# segment.net
KiCad netlist of a schematic drawn in EAGLE
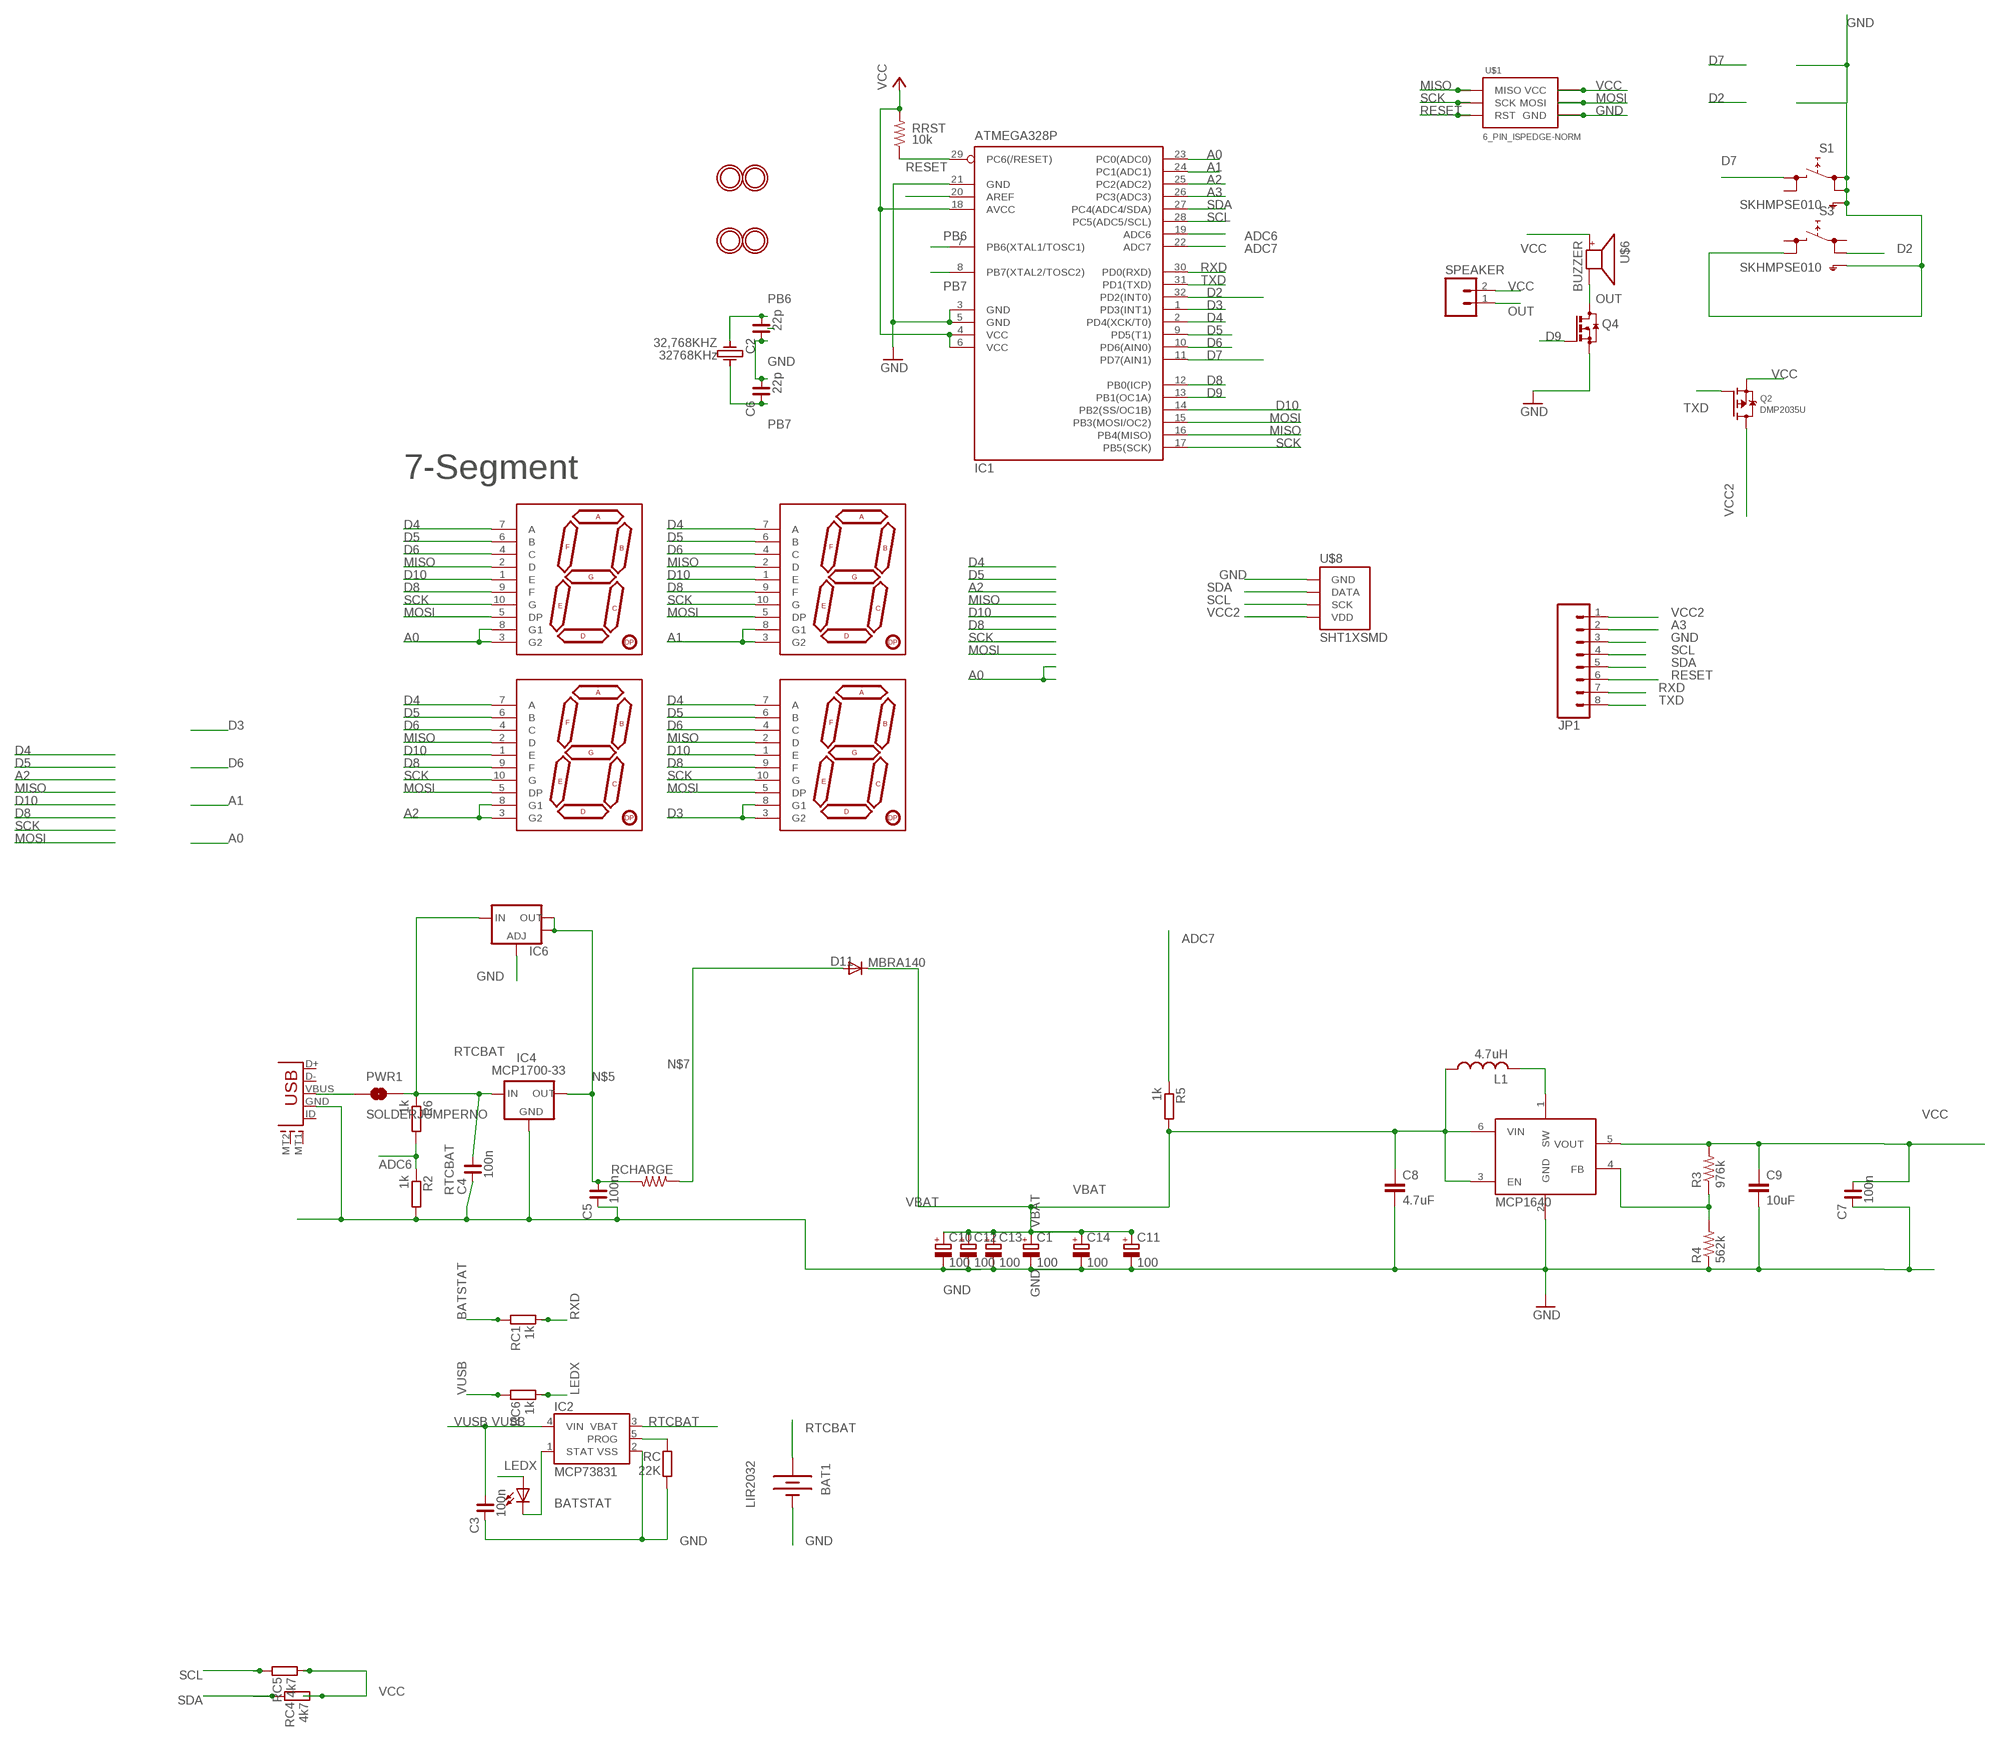
[diagram p0: schematic, sheet 1]

(export (version "E")
  (design (tool "Eeschema 10.0.6"))
  (components
    (comp (ref "32,768KHZ")
      (value "32768KHz")
      (footprint "eagle-import:KX-327LT")
      (libsource (lib "eagle-import") (part "CRYSTALL"))
    )
    (comp (ref "BAT1")
      (value "LIR2032")
      (footprint "eagle-import:BATTCOM_20MM_PTH_SMT")
      (libsource (lib "eagle-import") (part "BATTERYBATTCOM_20MM_PTH_SMT"))
    )
    (comp (ref "C1")
      (value "100")
      (footprint "eagle-import:TT5D11L")
      (libsource (lib "eagle-import") (part "CPOL-EUTT5D11L"))
    )
    (comp (ref "C2")
      (value "22p")
      (footprint "eagle-import:C0603")
      (libsource (lib "eagle-import") (part "C_0603"))
    )
    (comp (ref "C3")
      (value "100n")
      (footprint "eagle-import:C0603")
      (libsource (lib "eagle-import") (part "C_0603"))
    )
    (comp (ref "C4")
      (value "100n")
      (footprint "eagle-import:C0603")
      (libsource (lib "eagle-import") (part "C_0603"))
    )
    (comp (ref "C5")
      (value "100n")
      (footprint "eagle-import:C0603")
      (libsource (lib "eagle-import") (part "C_0603"))
    )
    (comp (ref "C6")
      (value "22p")
      (footprint "eagle-import:C0603")
      (libsource (lib "eagle-import") (part "C_0603"))
    )
    (comp (ref "C7")
      (value "100n")
      (footprint "eagle-import:C0603")
      (libsource (lib "eagle-import") (part "C_0603"))
    )
    (comp (ref "C8")
      (value "4.7uF")
      (footprint "eagle-import:0805")
      (libsource (lib "eagle-import") (part "CAP0805"))
    )
    (comp (ref "C9")
      (value "10uF")
      (footprint "eagle-import:0805")
      (libsource (lib "eagle-import") (part "CAP0805"))
    )
    (comp (ref "C10")
      (value "100")
      (footprint "eagle-import:TT5D11L")
      (libsource (lib "eagle-import") (part "CPOL-EUTT5D11L"))
    )
    (comp (ref "C11")
      (value "100")
      (footprint "eagle-import:TT5D11L")
      (libsource (lib "eagle-import") (part "CPOL-EUTT5D11L"))
    )
    (comp (ref "C12")
      (value "100")
      (footprint "eagle-import:TT5D11L")
      (libsource (lib "eagle-import") (part "CPOL-EUTT5D11L"))
    )
    (comp (ref "C13")
      (value "100")
      (footprint "eagle-import:TT5D11L")
      (libsource (lib "eagle-import") (part "CPOL-EUTT5D11L"))
    )
    (comp (ref "C14")
      (value "100")
      (footprint "eagle-import:TT5D11L")
      (libsource (lib "eagle-import") (part "CPOL-EUTT5D11L"))
    )
    (comp (ref "CHG")
      (value "0805")
      (footprint "eagle-import:CHIPLED_0603")
      (libsource (lib "eagle-import") (part "LEDCHIPLED_0603"))
    )
    (comp (ref "D11")
      (value "MBRA140")
      (footprint "eagle-import:SOD-323")
      (libsource (lib "eagle-import") (part "DIODESOD"))
    )
    (comp (ref "DIG1")
      (value "7-SEGMENT-DISPLAY-1\"-RED")
      (footprint "eagle-import:7-SEGMENT-SMD")
      (libsource (lib "eagle-import") (part "7-SEGMENT-DISPLAY-1{dblquote}-RED"))
    )
    (comp (ref "DIG2")
      (value "7-SEGMENT-DISPLAY-1\"-RED")
      (footprint "eagle-import:7-SEGMENT-SMD")
      (libsource (lib "eagle-import") (part "7-SEGMENT-DISPLAY-1{dblquote}-RED"))
    )
    (comp (ref "DIG3")
      (value "7-SEGMENT-DISPLAY-1\"-RED")
      (footprint "eagle-import:7-SEGMENT-SMD")
      (libsource (lib "eagle-import") (part "7-SEGMENT-DISPLAY-1{dblquote}-RED"))
    )
    (comp (ref "DIG4")
      (value "7-SEGMENT-DISPLAY-1\"-RED")
      (footprint "eagle-import:7-SEGMENT-SMD")
      (libsource (lib "eagle-import") (part "7-SEGMENT-DISPLAY-1{dblquote}-RED"))
    )
    (comp (ref "IC1")
      (value "ATMEGA328P")
      (footprint "eagle-import:TQFP32-08")
      (fields (field (name "MPN") "ATMEGA8-16AU"))
      (libsource (lib "eagle-import") (part "MEGA8-AI"))
    )
    (comp (ref "IC2")
      (value "MCP73831")
      (footprint "eagle-import:SOT23-5")
      (libsource (lib "eagle-import") (part "MCP73831"))
    )
    (comp (ref "IC4")
      (value "MCP1700-33")
      (footprint "eagle-import:SOT23")
      (libsource (lib "eagle-import") (part "MCP1700SOT233"))
    )
    (comp (ref "IC6")
      (value "V_REG_LM1117SOT223")
      (footprint "eagle-import:SOT223")
      (libsource (lib "eagle-import") (part "V_REG_LM1117SOT223"))
    )
    (comp (ref "JP1")
      (value "M08NO_SILK")
      (footprint "eagle-import:1X08_PIN1_NO_SILK")
      (libsource (lib "eagle-import") (part "M08NO_SILK"))
    )
    (comp (ref "L1")
      (value "4.7uH")
      (footprint "eagle-import:LQH44")
      (libsource (lib "eagle-import") (part "LLQH44P_P0"))
    )
    (comp (ref "PWR1")
      (value "SOLDERJUMPERNO")
      (footprint "eagle-import:SJ_2S-NO")
      (libsource (lib "eagle-import") (part "SOLDERJUMPERNO"))
    )
    (comp (ref "Q2")
      (value "DMP2035U")
      (footprint "eagle-import:SOT23-WIDE")
      (libsource (lib "eagle-import") (part "MOSFET-PWIDE"))
    )
    (comp (ref "Q4")
      (value "BSS123")
      (footprint "eagle-import:SOT23")
      (libsource (lib "eagle-import") (part "BSS123"))
    )
    (comp (ref "R2")
      (value "1k")
      (footprint "eagle-import:R0603")
      (libsource (lib "eagle-import") (part "R-EU_R0603"))
    )
    (comp (ref "R3")
      (value "976k")
      (footprint "eagle-import:0603-RES")
      (libsource (lib "eagle-import") (part "RESISTOR0603-RES"))
    )
    (comp (ref "R4")
      (value "562k")
      (footprint "eagle-import:0603-RES")
      (libsource (lib "eagle-import") (part "RESISTOR0603-RES"))
    )
    (comp (ref "R5")
      (value "1k")
      (footprint "eagle-import:R0603")
      (libsource (lib "eagle-import") (part "R-EU_R0603"))
    )
    (comp (ref "R6")
      (value "1k")
      (footprint "eagle-import:R0603")
      (libsource (lib "eagle-import") (part "R-EU_R0603"))
    )
    (comp (ref "RC")
      (value "22K")
      (footprint "eagle-import:R0603")
      (libsource (lib "eagle-import") (part "R-EU_R0603"))
    )
    (comp (ref "RC1")
      (value "1k")
      (footprint "eagle-import:R0603")
      (libsource (lib "eagle-import") (part "R-EU_R0603"))
    )
    (comp (ref "RC4")
      (value "4k7")
      (footprint "eagle-import:R0603")
      (libsource (lib "eagle-import") (part "R-EU_R0603"))
    )
    (comp (ref "RC5")
      (value "4k7")
      (footprint "eagle-import:R0603")
      (libsource (lib "eagle-import") (part "R-EU_R0603"))
    )
    (comp (ref "RC6")
      (value "1k")
      (footprint "eagle-import:R0603")
      (libsource (lib "eagle-import") (part "R-EU_R0603"))
    )
    (comp (ref "RCHARGE")
      (value "RESISTOR1206")
      (footprint "eagle-import:1206")
      (libsource (lib "eagle-import") (part "RESISTOR1206"))
    )
    (comp (ref "RRST")
      (value "10k")
      (footprint "eagle-import:R0603@1")
      (libsource (lib "eagle-import") (part "R-US_R0603"))
    )
    (comp (ref "S1")
      (value "SKHMPSE010")
      (footprint "eagle-import:SKHMPXE010")
      (libsource (lib "eagle-import") (part "SKHMPE010S"))
    )
    (comp (ref "S3")
      (value "SKHMPSE010")
      (footprint "eagle-import:SKHMPXE010")
      (libsource (lib "eagle-import") (part "SKHMPE010S"))
    )
    (comp (ref "SPEAKER")
      (value "M02PTH")
      (footprint "eagle-import:1X02")
      (libsource (lib "eagle-import") (part "M02PTH"))
    )
    (comp (ref "U$1")
      (value "6_PIN_ISPEDGE-NORM")
      (footprint "eagle-import:6_PIN_EDGE")
      (libsource (lib "eagle-import") (part "6_PIN_ISPEDGE-NORM"))
    )
    (comp (ref "U$2")
      (value "MOUNTINGHOLE2.0")
      (footprint "eagle-import:MOUNTINGHOLE_2.0_PLATED")
      (libsource (lib "eagle-import") (part "MOUNTINGHOLE2.0"))
    )
    (comp (ref "U$3")
      (value "MOUNTINGHOLE2.0")
      (footprint "eagle-import:MOUNTINGHOLE_2.0_PLATED")
      (libsource (lib "eagle-import") (part "MOUNTINGHOLE2.0"))
    )
    (comp (ref "U$4")
      (value "MOUNTINGHOLE2.0")
      (footprint "eagle-import:MOUNTINGHOLE_2.0_PLATED")
      (libsource (lib "eagle-import") (part "MOUNTINGHOLE2.0"))
    )
    (comp (ref "U$5")
      (value "MOUNTINGHOLE2.0")
      (footprint "eagle-import:MOUNTINGHOLE_2.0_PLATED")
      (libsource (lib "eagle-import") (part "MOUNTINGHOLE2.0"))
    )
    (comp (ref "U$6")
      (value "BUZZER")
      (footprint "eagle-import:SMT-8585-BUZZER")
      (libsource (lib "eagle-import") (part "BUZZER"))
    )
    (comp (ref "U$8")
      (value "SHT1XSMD")
      (footprint "eagle-import:SHT1X")
      (libsource (lib "eagle-import") (part "SHT1XSMD"))
    )
    (comp (ref "U2")
      (value "MCP1640")
      (footprint "eagle-import:SOT23-6")
      (libsource (lib "eagle-import") (part "MCP1640"))
    )
    (comp (ref "USB2")
      (value "USB-MICROBLARGEPAD")
      (footprint "eagle-import:USB-MICROB_LARGEPAD")
      (libsource (lib "eagle-import") (part "USB-MICROBLARGEPAD"))
    )
  )
  (nets
    (net (code "1") (name "/A0") (class "Default")
      (node (ref "DIG1") (pin "3") (pinfunction "G2_3") (pintype "bidirectional"))
      (node (ref "DIG1") (pin "8") (pinfunction "G1_8") (pintype "bidirectional"))
      (node (ref "IC1") (pin "23") (pinfunction "PC0(ADC0)_23") (pintype "bidirectional"))
    )
    (net (code "2") (name "/A1") (class "Default")
      (node (ref "DIG2") (pin "3") (pinfunction "G2_3") (pintype "bidirectional"))
      (node (ref "DIG2") (pin "8") (pinfunction "G1_8") (pintype "bidirectional"))
      (node (ref "IC1") (pin "24") (pinfunction "PC1(ADC1)_24") (pintype "bidirectional"))
    )
    (net (code "3") (name "/A2") (class "Default")
      (node (ref "DIG3") (pin "3") (pinfunction "G2_3") (pintype "bidirectional"))
      (node (ref "DIG3") (pin "8") (pinfunction "G1_8") (pintype "bidirectional"))
      (node (ref "IC1") (pin "25") (pinfunction "PC2(ADC2)_25") (pintype "bidirectional"))
    )
    (net (code "4") (name "/A3") (class "Default")
      (node (ref "IC1") (pin "26") (pinfunction "PC3(ADC3)_26") (pintype "bidirectional"))
      (node (ref "JP1") (pin "2") (pinfunction "2_2") (pintype "passive"))
    )
    (net (code "5") (name "/ADC6") (class "Default")
      (node (ref "IC1") (pin "19") (pinfunction "ADC6_19") (pintype "bidirectional"))
      (node (ref "R2") (pin "1") (pinfunction "1_1") (pintype "passive"))
      (node (ref "R6") (pin "2") (pinfunction "2_2") (pintype "passive"))
    )
    (net (code "6") (name "/ADC7") (class "Default")
      (node (ref "IC1") (pin "22") (pinfunction "ADC7_22") (pintype "bidirectional"))
      (node (ref "R5") (pin "1") (pinfunction "1_1") (pintype "passive"))
    )
    (net (code "7") (name "/BATSTAT") (class "Default")
      (node (ref "CHG") (pin "C") (pinfunction "C_C") (pintype "passive"))
      (node (ref "IC2") (pin "1") (pinfunction "STAT_1") (pintype "output"))
      (node (ref "RC1") (pin "2") (pinfunction "2_2") (pintype "passive"))
    )
    (net (code "8") (name "/D2") (class "Default")
      (node (ref "IC1") (pin "32") (pinfunction "PD2(INT0)_32") (pintype "bidirectional"))
      (node (ref "S3") (pin "2") (pinfunction "1.2_2") (pintype "passive"))
    )
    (net (code "9") (name "/D3") (class "Default")
      (node (ref "DIG4") (pin "3") (pinfunction "G2_3") (pintype "bidirectional"))
      (node (ref "DIG4") (pin "8") (pinfunction "G1_8") (pintype "bidirectional"))
      (node (ref "IC1") (pin "1") (pinfunction "PD3(INT1)_1") (pintype "bidirectional"))
    )
    (net (code "10") (name "/D4") (class "Default")
      (node (ref "DIG1") (pin "7") (pinfunction "A_7") (pintype "bidirectional"))
      (node (ref "DIG2") (pin "7") (pinfunction "A_7") (pintype "bidirectional"))
      (node (ref "DIG3") (pin "7") (pinfunction "A_7") (pintype "bidirectional"))
      (node (ref "DIG4") (pin "7") (pinfunction "A_7") (pintype "bidirectional"))
      (node (ref "IC1") (pin "2") (pinfunction "PD4(XCK/T0)_2") (pintype "bidirectional"))
    )
    (net (code "11") (name "/D5") (class "Default")
      (node (ref "DIG1") (pin "6") (pinfunction "B_6") (pintype "bidirectional"))
      (node (ref "DIG2") (pin "6") (pinfunction "B_6") (pintype "bidirectional"))
      (node (ref "DIG3") (pin "6") (pinfunction "B_6") (pintype "bidirectional"))
      (node (ref "DIG4") (pin "6") (pinfunction "B_6") (pintype "bidirectional"))
      (node (ref "IC1") (pin "9") (pinfunction "PD5(T1)_9") (pintype "bidirectional"))
    )
    (net (code "12") (name "/D6") (class "Default")
      (node (ref "DIG1") (pin "4") (pinfunction "C_4") (pintype "bidirectional"))
      (node (ref "DIG2") (pin "4") (pinfunction "C_4") (pintype "bidirectional"))
      (node (ref "DIG3") (pin "4") (pinfunction "C_4") (pintype "bidirectional"))
      (node (ref "DIG4") (pin "4") (pinfunction "C_4") (pintype "bidirectional"))
      (node (ref "IC1") (pin "10") (pinfunction "PD6(AIN0)_10") (pintype "bidirectional"))
    )
    (net (code "13") (name "/D7") (class "Default")
      (node (ref "IC1") (pin "11") (pinfunction "PD7(AIN1)_11") (pintype "bidirectional"))
      (node (ref "S1") (pin "3") (pinfunction "2.1_3") (pintype "passive"))
    )
    (net (code "14") (name "/D8") (class "Default")
      (node (ref "DIG1") (pin "9") (pinfunction "F_9") (pintype "bidirectional"))
      (node (ref "DIG2") (pin "9") (pinfunction "F_9") (pintype "bidirectional"))
      (node (ref "DIG3") (pin "9") (pinfunction "F_9") (pintype "bidirectional"))
      (node (ref "DIG4") (pin "9") (pinfunction "F_9") (pintype "bidirectional"))
      (node (ref "IC1") (pin "12") (pinfunction "PB0(ICP)_12") (pintype "bidirectional"))
    )
    (net (code "15") (name "/D9") (class "Default")
      (node (ref "IC1") (pin "13") (pinfunction "PB1(OC1A)_13") (pintype "bidirectional"))
      (node (ref "Q4") (pin "1") (pinfunction "G_1") (pintype "passive"))
    )
    (net (code "16") (name "/D10") (class "Default")
      (node (ref "DIG1") (pin "1") (pinfunction "E_1") (pintype "bidirectional"))
      (node (ref "DIG2") (pin "1") (pinfunction "E_1") (pintype "bidirectional"))
      (node (ref "DIG3") (pin "1") (pinfunction "E_1") (pintype "bidirectional"))
      (node (ref "DIG4") (pin "1") (pinfunction "E_1") (pintype "bidirectional"))
      (node (ref "IC1") (pin "14") (pinfunction "PB2(SS/OC1B)_14") (pintype "bidirectional"))
    )
    (net (code "17") (name "/LEDX") (class "Default")
      (node (ref "CHG") (pin "A") (pinfunction "A_A") (pintype "passive"))
      (node (ref "RC6") (pin "1") (pinfunction "1_1") (pintype "passive"))
    )
    (net (code "18") (name "/MISO") (class "Default")
      (node (ref "DIG1") (pin "2") (pinfunction "D_2") (pintype "bidirectional"))
      (node (ref "DIG2") (pin "2") (pinfunction "D_2") (pintype "bidirectional"))
      (node (ref "DIG3") (pin "2") (pinfunction "D_2") (pintype "bidirectional"))
      (node (ref "DIG4") (pin "2") (pinfunction "D_2") (pintype "bidirectional"))
      (node (ref "IC1") (pin "16") (pinfunction "PB4(MISO)_16") (pintype "bidirectional"))
      (node (ref "U$1") (pin "1") (pinfunction "MISO_1") (pintype "bidirectional"))
    )
    (net (code "19") (name "/MOSI") (class "Default")
      (node (ref "DIG1") (pin "5") (pinfunction "DP_5") (pintype "bidirectional"))
      (node (ref "DIG2") (pin "5") (pinfunction "DP_5") (pintype "bidirectional"))
      (node (ref "DIG3") (pin "5") (pinfunction "DP_5") (pintype "bidirectional"))
      (node (ref "DIG4") (pin "5") (pinfunction "DP_5") (pintype "bidirectional"))
      (node (ref "IC1") (pin "15") (pinfunction "PB3(MOSI/OC2)_15") (pintype "bidirectional"))
      (node (ref "U$1") (pin "4") (pinfunction "MOSI_4") (pintype "bidirectional"))
    )
    (net (code "20") (name "/N$5") (class "Default")
      (node (ref "C5") (pin "1") (pinfunction "1_1") (pintype "passive"))
      (node (ref "IC4") (pin "2") (pinfunction "OUT_2") (pintype "passive"))
      (node (ref "IC6") (pin "2") (pinfunction "OUT_2") (pintype "output"))
      (node (ref "IC6") (pin "4") (pinfunction "OUT_4") (pintype "output"))
      (node (ref "RCHARGE") (pin "2") (pinfunction "2_2") (pintype "passive"))
    )
    (net (code "21") (name "/N$7") (class "Default")
      (node (ref "D11") (pin "2") (pinfunction "A_2") (pintype "passive"))
      (node (ref "RCHARGE") (pin "1") (pinfunction "1_1") (pintype "passive"))
    )
    (net (code "22") (name "/OUT") (class "Default")
      (node (ref "Q4") (pin "3") (pinfunction "D_3") (pintype "passive"))
      (node (ref "SPEAKER") (pin "1") (pinfunction "1_1") (pintype "passive"))
      (node (ref "U$6") (pin "-") (pinfunction "-_-") (pintype "passive"))
    )
    (net (code "23") (name "/PB6") (class "Default")
      (node (ref "32,768KHZ") (pin "4") (pinfunction "P$2_4") (pintype "bidirectional"))
      (node (ref "C2") (pin "1") (pinfunction "1_1") (pintype "passive"))
      (node (ref "IC1") (pin "7") (pinfunction "PB6(XTAL1/TOSC1)_7") (pintype "bidirectional"))
    )
    (net (code "24") (name "/PB7") (class "Default")
      (node (ref "32,768KHZ") (pin "1") (pinfunction "P$1_1") (pintype "bidirectional"))
      (node (ref "C6") (pin "2") (pinfunction "2_2") (pintype "passive"))
      (node (ref "IC1") (pin "8") (pinfunction "PB7(XTAL2/TOSC2)_8") (pintype "bidirectional"))
    )
    (net (code "25") (name "/RESET") (class "Default")
      (node (ref "IC1") (pin "29") (pinfunction "PC6(/RESET)_29") (pintype "bidirectional"))
      (node (ref "JP1") (pin "6") (pinfunction "6_6") (pintype "passive"))
      (node (ref "RRST") (pin "1") (pinfunction "1_1") (pintype "passive"))
      (node (ref "U$1") (pin "5") (pinfunction "RST_5") (pintype "bidirectional"))
    )
    (net (code "26") (name "/RTCBAT") (class "Default")
      (node (ref "BAT1") (pin "P$2") (pinfunction "+_P$2") (pintype "power_in"))
      (node (ref "C4") (pin "1") (pinfunction "1_1") (pintype "passive"))
      (node (ref "IC2") (pin "3") (pinfunction "VBAT_3") (pintype "power_in"))
      (node (ref "IC4") (pin "3") (pinfunction "IN_3") (pintype "input"))
      (node (ref "IC6") (pin "3") (pinfunction "IN_3") (pintype "input"))
      (node (ref "PWR1") (pin "2") (pinfunction "2_2") (pintype "passive"))
      (node (ref "R6") (pin "1") (pinfunction "1_1") (pintype "passive"))
    )
    (net (code "27") (name "/RXD") (class "Default")
      (node (ref "IC1") (pin "30") (pinfunction "PD0(RXD)_30") (pintype "bidirectional"))
      (node (ref "JP1") (pin "7") (pinfunction "7_7") (pintype "passive"))
      (node (ref "RC1") (pin "1") (pinfunction "1_1") (pintype "passive"))
    )
    (net (code "28") (name "/SCK") (class "Default")
      (node (ref "DIG1") (pin "10") (pinfunction "G_10") (pintype "bidirectional"))
      (node (ref "DIG2") (pin "10") (pinfunction "G_10") (pintype "bidirectional"))
      (node (ref "DIG3") (pin "10") (pinfunction "G_10") (pintype "bidirectional"))
      (node (ref "DIG4") (pin "10") (pinfunction "G_10") (pintype "bidirectional"))
      (node (ref "IC1") (pin "17") (pinfunction "PB5(SCK)_17") (pintype "bidirectional"))
      (node (ref "U$1") (pin "3") (pinfunction "SCK_3") (pintype "bidirectional"))
    )
    (net (code "29") (name "/SCL") (class "Default")
      (node (ref "IC1") (pin "28") (pinfunction "PC5(ADC5/SCL)_28") (pintype "bidirectional"))
      (node (ref "JP1") (pin "4") (pinfunction "4_4") (pintype "passive"))
      (node (ref "RC5") (pin "2") (pinfunction "2_2") (pintype "passive"))
      (node (ref "U$8") (pin "3") (pinfunction "SCK_3") (pintype "input"))
    )
    (net (code "30") (name "/SDA") (class "Default")
      (node (ref "IC1") (pin "27") (pinfunction "PC4(ADC4/SDA)_27") (pintype "bidirectional"))
      (node (ref "JP1") (pin "5") (pinfunction "5_5") (pintype "passive"))
      (node (ref "RC4") (pin "2") (pinfunction "2_2") (pintype "passive"))
      (node (ref "U$8") (pin "2") (pinfunction "DATA_2") (pintype "bidirectional"))
    )
    (net (code "31") (name "/TXD") (class "Default")
      (node (ref "IC1") (pin "31") (pinfunction "PD1(TXD)_31") (pintype "bidirectional"))
      (node (ref "JP1") (pin "8") (pinfunction "8_8") (pintype "passive"))
      (node (ref "Q2") (pin "1") (pinfunction "G_1") (pintype "passive"))
    )
    (net (code "32") (name "/VBAT") (class "Default")
      (node (ref "C1") (pin "+") (pinfunction "+_+") (pintype "passive"))
      (node (ref "C10") (pin "+") (pinfunction "+_+") (pintype "passive"))
      (node (ref "C11") (pin "+") (pinfunction "+_+") (pintype "passive"))
      (node (ref "C12") (pin "+") (pinfunction "+_+") (pintype "passive"))
      (node (ref "C13") (pin "+") (pinfunction "+_+") (pintype "passive"))
      (node (ref "C14") (pin "+") (pinfunction "+_+") (pintype "passive"))
      (node (ref "C8") (pin "1") (pinfunction "1_1") (pintype "passive"))
      (node (ref "D11") (pin "1") (pinfunction "C_1") (pintype "passive"))
      (node (ref "L1") (pin "P$1") (pinfunction "1_P$1") (pintype "passive"))
      (node (ref "R5") (pin "2") (pinfunction "2_2") (pintype "passive"))
      (node (ref "U2") (pin "3") (pinfunction "EN_3") (pintype "input"))
      (node (ref "U2") (pin "6") (pinfunction "VIN_6") (pintype "input"))
    )
    (net (code "33") (name "/VCC2") (class "Default")
      (node (ref "JP1") (pin "1") (pinfunction "1_1") (pintype "passive"))
      (node (ref "Q2") (pin "3") (pinfunction "D_3") (pintype "passive"))
      (node (ref "U$8") (pin "4") (pinfunction "VDD_4") (pintype "power_in"))
    )
    (net (code "34") (name "/VUSB") (class "Default")
      (node (ref "C3") (pin "1") (pinfunction "1_1") (pintype "passive"))
      (node (ref "IC2") (pin "4") (pinfunction "VIN_4") (pintype "power_in"))
      (node (ref "PWR1") (pin "1") (pinfunction "1_1") (pintype "passive"))
      (node (ref "RC6") (pin "2") (pinfunction "2_2") (pintype "passive"))
      (node (ref "USB2") (pin "VBUS") (pinfunction "VBUS_VBUS") (pintype "bidirectional"))
    )
    (net (code "35") (name "GND") (class "Default")
      (node (ref "BAT1") (pin "P$1") (pinfunction "-_P$1") (pintype "power_in"))
      (node (ref "C1") (pin "-") (pinfunction "-_-") (pintype "passive"))
      (node (ref "C10") (pin "-") (pinfunction "-_-") (pintype "passive"))
      (node (ref "C11") (pin "-") (pinfunction "-_-") (pintype "passive"))
      (node (ref "C12") (pin "-") (pinfunction "-_-") (pintype "passive"))
      (node (ref "C13") (pin "-") (pinfunction "-_-") (pintype "passive"))
      (node (ref "C14") (pin "-") (pinfunction "-_-") (pintype "passive"))
      (node (ref "C2") (pin "2") (pinfunction "2_2") (pintype "passive"))
      (node (ref "C3") (pin "2") (pinfunction "2_2") (pintype "passive"))
      (node (ref "C4") (pin "2") (pinfunction "2_2") (pintype "passive"))
      (node (ref "C5") (pin "2") (pinfunction "2_2") (pintype "passive"))
      (node (ref "C6") (pin "1") (pinfunction "1_1") (pintype "passive"))
      (node (ref "C7") (pin "2") (pinfunction "2_2") (pintype "passive"))
      (node (ref "C8") (pin "2") (pinfunction "2_2") (pintype "passive"))
      (node (ref "C9") (pin "2") (pinfunction "2_2") (pintype "passive"))
      (node (ref "IC1") (pin "21") (pinfunction "GND_21") (pintype "power_in"))
      (node (ref "IC1") (pin "3") (pinfunction "GND_3") (pintype "power_in"))
      (node (ref "IC1") (pin "5") (pinfunction "GND_5") (pintype "power_in"))
      (node (ref "IC2") (pin "2") (pinfunction "VSS_2") (pintype "power_in"))
      (node (ref "IC4") (pin "1") (pinfunction "GND_1") (pintype "input"))
      (node (ref "IC6") (pin "1") (pinfunction "ADJ_1") (pintype "input"))
      (node (ref "JP1") (pin "3") (pinfunction "3_3") (pintype "passive"))
      (node (ref "Q4") (pin "2") (pinfunction "S_2") (pintype "passive"))
      (node (ref "R2") (pin "2") (pinfunction "2_2") (pintype "passive"))
      (node (ref "R4") (pin "1") (pinfunction "1_1") (pintype "passive"))
      (node (ref "RC") (pin "1") (pinfunction "1_1") (pintype "passive"))
      (node (ref "S1") (pin "1") (pinfunction "1.1_1") (pintype "passive"))
      (node (ref "S1") (pin "2") (pinfunction "1.2_2") (pintype "passive"))
      (node (ref "S1") (pin "5") (pinfunction "SH_5") (pintype "passive"))
      (node (ref "S3") (pin "4") (pinfunction "2.2_4") (pintype "passive"))
      (node (ref "S3") (pin "5") (pinfunction "SH_5") (pintype "passive"))
      (node (ref "U$1") (pin "6") (pinfunction "GND_6") (pintype "power_in"))
      (node (ref "U$8") (pin "1") (pinfunction "GND_1") (pintype "power_in"))
      (node (ref "U2") (pin "2") (pinfunction "GND_2") (pintype "power_in"))
      (node (ref "USB2") (pin "GND") (pinfunction "GND_GND") (pintype "bidirectional"))
    )
    (net (code "36") (name "Net-(IC2-PROG)") (class "Default")
      (node (ref "IC2") (pin "5") (pinfunction "PROG_5") (pintype "input"))
      (node (ref "RC") (pin "2") (pinfunction "2_2") (pintype "passive"))
    )
    (net (code "37") (name "Net-(L1-2)") (class "Default")
      (node (ref "L1") (pin "P$2") (pinfunction "2_P$2") (pintype "passive"))
      (node (ref "U2") (pin "1") (pinfunction "SW_1") (pintype "output"))
    )
    (net (code "38") (name "Net-(U2-FB)") (class "Default")
      (node (ref "R3") (pin "1") (pinfunction "1_1") (pintype "passive"))
      (node (ref "R4") (pin "2") (pinfunction "2_2") (pintype "passive"))
      (node (ref "U2") (pin "4") (pinfunction "FB_4") (pintype "input"))
    )
    (net (code "39") (name "VCC") (class "Default")
      (node (ref "C7") (pin "1") (pinfunction "1_1") (pintype "passive"))
      (node (ref "C9") (pin "1") (pinfunction "1_1") (pintype "passive"))
      (node (ref "IC1") (pin "18") (pinfunction "AVCC_18") (pintype "power_in"))
      (node (ref "IC1") (pin "4") (pinfunction "VCC_4") (pintype "power_in"))
      (node (ref "IC1") (pin "6") (pinfunction "VCC_6") (pintype "power_in"))
      (node (ref "Q2") (pin "2") (pinfunction "S_2") (pintype "passive"))
      (node (ref "R3") (pin "2") (pinfunction "2_2") (pintype "passive"))
      (node (ref "RC4") (pin "1") (pinfunction "1_1") (pintype "passive"))
      (node (ref "RC5") (pin "1") (pinfunction "1_1") (pintype "passive"))
      (node (ref "RRST") (pin "2") (pinfunction "2_2") (pintype "passive"))
      (node (ref "SPEAKER") (pin "2") (pinfunction "2_2") (pintype "passive"))
      (node (ref "U$1") (pin "2") (pinfunction "VCC_2") (pintype "power_in"))
      (node (ref "U$6") (pin "+") (pinfunction "+_+") (pintype "passive"))
      (node (ref "U2") (pin "5") (pinfunction "VOUT_5") (pintype "output"))
    )
    (net (code "40") (name "unconnected-(IC1-AREF-Pad20)") (class "Default")
      (node (ref "IC1") (pin "20") (pinfunction "AREF_20") (pintype "passive"))
    )
    (net (code "41") (name "unconnected-(S1-2.2-Pad4)") (class "Default")
      (node (ref "S1") (pin "4") (pinfunction "2.2_4") (pintype "passive"))
    )
    (net (code "42") (name "unconnected-(S3-1.1-Pad1)") (class "Default")
      (node (ref "S3") (pin "1") (pinfunction "1.1_1") (pintype "passive"))
    )
    (net (code "43") (name "unconnected-(S3-2.1-Pad3)") (class "Default")
      (node (ref "S3") (pin "3") (pinfunction "2.1_3") (pintype "passive"))
    )
    (net (code "44") (name "unconnected-(USB2-PadD+)") (class "Default")
      (node (ref "USB2") (pin "D+") (pinfunction "D+_D+") (pintype "bidirectional"))
    )
    (net (code "45") (name "unconnected-(USB2-PadD-)") (class "Default")
      (node (ref "USB2") (pin "D-") (pinfunction "D-_D-") (pintype "bidirectional"))
    )
    (net (code "46") (name "unconnected-(USB2-PadID)") (class "Default")
      (node (ref "USB2") (pin "ID") (pinfunction "ID_ID") (pintype "bidirectional"))
    )
    (net (code "47") (name "unconnected-(USB2-SHEILD1-PadMT1)") (class "Default")
      (node (ref "USB2") (pin "MT1") (pinfunction "SHEILD1_MT1") (pintype "bidirectional"))
    )
    (net (code "48") (name "unconnected-(USB2-SHEILD2-PadMT2)") (class "Default")
      (node (ref "USB2") (pin "MT2") (pinfunction "SHEILD2_MT2") (pintype "bidirectional"))
    )
  )
)
